# PROC054D_System_LED.net
KiCad netlist of a schematic drawn in Altium Designer
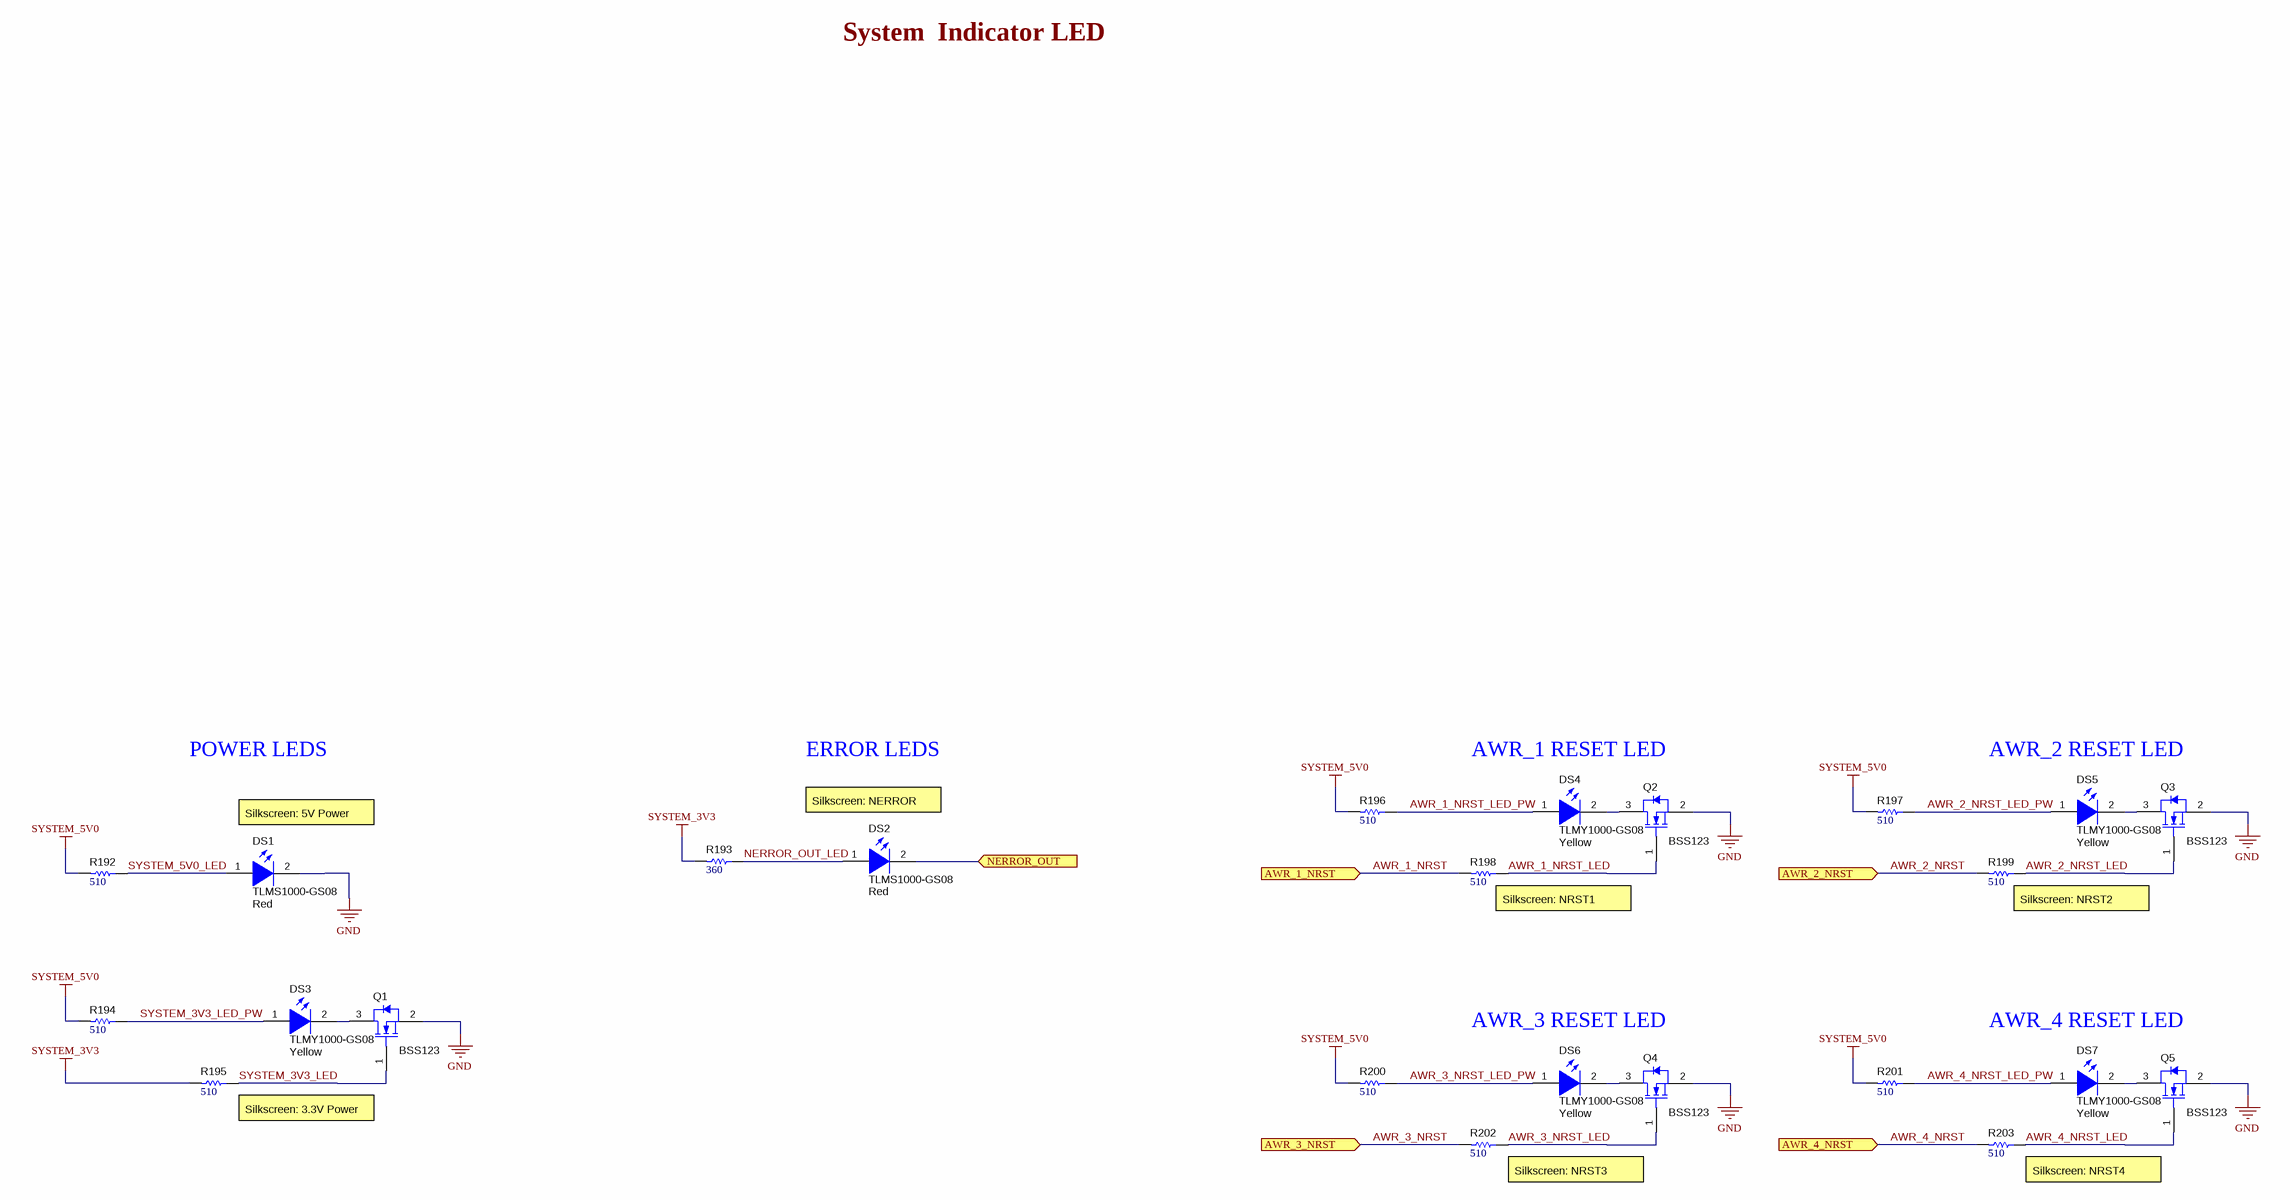
[diagram p0: PROC054D_System_LED.SchDoc]

(export (version "E")
  (design (tool "Eeschema 10.0.6"))
  (components
    (comp (ref "DS1")
      (value "TLMS1000-GS08")
      (footprint "TLMx1000_Red")
      (description "LED, Red, SMD")
      (fields
        (field (name "ALTIUM_VALUE") "Red")
        (field (name "MANUFACTURER") "Vishay-Semiconductor")
        (field (name "PUBLISHER") "Texas Instruments")
      )
      (libsource (lib "Altium Vault - TI") (part "LED"))
    )
    (comp (ref "DS2")
      (value "TLMS1000-GS08")
      (footprint "TLMx1000_Red")
      (description "LED, Red, SMD")
      (fields
        (field (name "ALTIUM_VALUE") "Red")
        (field (name "MANUFACTURER") "Vishay-Semiconductor")
        (field (name "PUBLISHER") "Texas Instruments")
      )
      (libsource (lib "Altium Vault - TI") (part "LED"))
    )
    (comp (ref "DS3")
      (value "TLMY1000-GS08")
      (footprint "TLMx1000_Yellow")
      (description "LED, Yellow, SMD")
      (fields
        (field (name "ALTIUM_VALUE") "Yellow")
        (field (name "MANUFACTURER") "Vishay-Semiconductor")
        (field (name "PUBLISHER") "Texas Instruments")
      )
      (libsource (lib "Altium Vault - TI") (part "LED"))
    )
    (comp (ref "DS4")
      (value "TLMY1000-GS08")
      (footprint "TLMx1000_Yellow")
      (description "LED, Yellow, SMD")
      (fields
        (field (name "ALTIUM_VALUE") "Yellow")
        (field (name "MANUFACTURER") "Vishay-Semiconductor")
        (field (name "PUBLISHER") "Texas Instruments")
      )
      (libsource (lib "Altium Vault - TI") (part "LED"))
    )
    (comp (ref "DS5")
      (value "TLMY1000-GS08")
      (footprint "TLMx1000_Yellow")
      (description "LED, Yellow, SMD")
      (fields
        (field (name "ALTIUM_VALUE") "Yellow")
        (field (name "MANUFACTURER") "Vishay-Semiconductor")
        (field (name "PUBLISHER") "Texas Instruments")
      )
      (libsource (lib "Altium Vault - TI") (part "LED"))
    )
    (comp (ref "DS6")
      (value "TLMY1000-GS08")
      (footprint "TLMx1000_Yellow")
      (description "LED, Yellow, SMD")
      (fields
        (field (name "ALTIUM_VALUE") "Yellow")
        (field (name "MANUFACTURER") "Vishay-Semiconductor")
        (field (name "PUBLISHER") "Texas Instruments")
      )
      (libsource (lib "Altium Vault - TI") (part "LED"))
    )
    (comp (ref "DS7")
      (value "TLMY1000-GS08")
      (footprint "TLMx1000_Yellow")
      (description "LED, Yellow, SMD")
      (fields
        (field (name "ALTIUM_VALUE") "Yellow")
        (field (name "MANUFACTURER") "Vishay-Semiconductor")
        (field (name "PUBLISHER") "Texas Instruments")
      )
      (libsource (lib "Altium Vault - TI") (part "LED"))
    )
    (comp (ref "Q1")
      (value "BSS123")
      (footprint "SOT-23")
      (description "MOSFET, N-CH, 100 V, 0.17 A, SOT-23")
      (fields
        (field (name "MANUFACTURER") "Fairchild Semiconductor")
        (field (name "PUBLISHER") "Texas Instruments")
      )
      (libsource (lib "Altium Vault - TI") (part "MOSFET_N_D3G1S2"))
    )
    (comp (ref "Q2")
      (value "BSS123")
      (footprint "SOT-23")
      (description "MOSFET, N-CH, 100 V, 0.17 A, SOT-23")
      (fields
        (field (name "MANUFACTURER") "Fairchild Semiconductor")
        (field (name "PUBLISHER") "Texas Instruments")
      )
      (libsource (lib "Altium Vault - TI") (part "MOSFET_N_D3G1S2"))
    )
    (comp (ref "Q3")
      (value "BSS123")
      (footprint "SOT-23")
      (description "MOSFET, N-CH, 100 V, 0.17 A, SOT-23")
      (fields
        (field (name "MANUFACTURER") "Fairchild Semiconductor")
        (field (name "PUBLISHER") "Texas Instruments")
      )
      (libsource (lib "Altium Vault - TI") (part "MOSFET_N_D3G1S2"))
    )
    (comp (ref "Q4")
      (value "BSS123")
      (footprint "SOT-23")
      (description "MOSFET, N-CH, 100 V, 0.17 A, SOT-23")
      (fields
        (field (name "MANUFACTURER") "Fairchild Semiconductor")
        (field (name "PUBLISHER") "Texas Instruments")
      )
      (libsource (lib "Altium Vault - TI") (part "MOSFET_N_D3G1S2"))
    )
    (comp (ref "Q5")
      (value "BSS123")
      (footprint "SOT-23")
      (description "MOSFET, N-CH, 100 V, 0.17 A, SOT-23")
      (fields
        (field (name "MANUFACTURER") "Fairchild Semiconductor")
        (field (name "PUBLISHER") "Texas Instruments")
      )
      (libsource (lib "Altium Vault - TI") (part "MOSFET_N_D3G1S2"))
    )
    (comp (ref "R192")
      (value "ERJ-2GEJ511X")
      (footprint "0402")
      (description "RES, 510, 5%, 0.1 W, AEC-Q200 Grade 0, 0402")
      (fields (field (name "MANUFACTURER") "Panasonic") (field (name "VALUEDISPLAYED") "510"))
      (libsource (lib "Altium Vault - TI") (part "Resistor"))
    )
    (comp (ref "R193")
      (value "ERJ-2GEJ361X")
      (footprint "0402")
      (description "RES, 360, 5%, 0.1 W, AEC-Q200 Grade 0, 0402")
      (fields (field (name "MANUFACTURER") "Panasonic") (field (name "VALUEDISPLAYED") "360"))
      (libsource (lib "Altium Vault - TI") (part "Resistor"))
    )
    (comp (ref "R194")
      (value "ERJ-2GEJ511X")
      (footprint "0402")
      (description "RES, 510, 5%, 0.1 W, AEC-Q200 Grade 0, 0402")
      (fields (field (name "MANUFACTURER") "Panasonic") (field (name "VALUEDISPLAYED") "510"))
      (libsource (lib "Altium Vault - TI") (part "Resistor"))
    )
    (comp (ref "R195")
      (value "ERJ-2GEJ511X")
      (footprint "0402")
      (description "RES, 510, 5%, 0.1 W, AEC-Q200 Grade 0, 0402")
      (fields (field (name "MANUFACTURER") "Panasonic") (field (name "VALUEDISPLAYED") "510"))
      (libsource (lib "Altium Vault - TI") (part "Resistor"))
    )
    (comp (ref "R196")
      (value "ERJ-2GEJ511X")
      (footprint "0402")
      (description "RES, 510, 5%, 0.1 W, AEC-Q200 Grade 0, 0402")
      (fields (field (name "MANUFACTURER") "Panasonic") (field (name "VALUEDISPLAYED") "510"))
      (libsource (lib "Altium Vault - TI") (part "Resistor"))
    )
    (comp (ref "R197")
      (value "ERJ-2GEJ511X")
      (footprint "0402")
      (description "RES, 510, 5%, 0.1 W, AEC-Q200 Grade 0, 0402")
      (fields (field (name "MANUFACTURER") "Panasonic") (field (name "VALUEDISPLAYED") "510"))
      (libsource (lib "Altium Vault - TI") (part "Resistor"))
    )
    (comp (ref "R198")
      (value "ERJ-2GEJ511X")
      (footprint "0402")
      (description "RES, 510, 5%, 0.1 W, AEC-Q200 Grade 0, 0402")
      (fields (field (name "MANUFACTURER") "Panasonic") (field (name "VALUEDISPLAYED") "510"))
      (libsource (lib "Altium Vault - TI") (part "Resistor"))
    )
    (comp (ref "R199")
      (value "ERJ-2GEJ511X")
      (footprint "0402")
      (description "RES, 510, 5%, 0.1 W, AEC-Q200 Grade 0, 0402")
      (fields (field (name "MANUFACTURER") "Panasonic") (field (name "VALUEDISPLAYED") "510"))
      (libsource (lib "Altium Vault - TI") (part "Resistor"))
    )
    (comp (ref "R200")
      (value "ERJ-2GEJ511X")
      (footprint "0402")
      (description "RES, 510, 5%, 0.1 W, AEC-Q200 Grade 0, 0402")
      (fields (field (name "MANUFACTURER") "Panasonic") (field (name "VALUEDISPLAYED") "510"))
      (libsource (lib "Altium Vault - TI") (part "Resistor"))
    )
    (comp (ref "R201")
      (value "ERJ-2GEJ511X")
      (footprint "0402")
      (description "RES, 510, 5%, 0.1 W, AEC-Q200 Grade 0, 0402")
      (fields (field (name "MANUFACTURER") "Panasonic") (field (name "VALUEDISPLAYED") "510"))
      (libsource (lib "Altium Vault - TI") (part "Resistor"))
    )
    (comp (ref "R202")
      (value "ERJ-2GEJ511X")
      (footprint "0402")
      (description "RES, 510, 5%, 0.1 W, AEC-Q200 Grade 0, 0402")
      (fields (field (name "MANUFACTURER") "Panasonic") (field (name "VALUEDISPLAYED") "510"))
      (libsource (lib "Altium Vault - TI") (part "Resistor"))
    )
    (comp (ref "R203")
      (value "ERJ-2GEJ511X")
      (footprint "0402")
      (description "RES, 510, 5%, 0.1 W, AEC-Q200 Grade 0, 0402")
      (fields (field (name "MANUFACTURER") "Panasonic") (field (name "VALUEDISPLAYED") "510"))
      (libsource (lib "Altium Vault - TI") (part "Resistor"))
    )
  )
  (nets
    (net (code "1") (name "/AWR_1_NRST") (class "Default")
      (node (ref "R198") (pin "2") (pinfunction "2_2") (pintype "passive"))
    )
    (net (code "2") (name "/AWR_1_NRST_LED") (class "Default")
      (node (ref "Q2") (pin "1") (pinfunction "G_1") (pintype "passive"))
      (node (ref "R198") (pin "1") (pinfunction "1_1") (pintype "passive"))
    )
    (net (code "3") (name "/AWR_1_NRST_LED_PW") (class "Default")
      (node (ref "DS4") (pin "1") (pinfunction "A_1") (pintype "passive"))
      (node (ref "R196") (pin "1") (pinfunction "1_1") (pintype "passive"))
    )
    (net (code "4") (name "/AWR_2_NRST") (class "Default")
      (node (ref "R199") (pin "2") (pinfunction "2_2") (pintype "passive"))
    )
    (net (code "5") (name "/AWR_2_NRST_LED") (class "Default")
      (node (ref "Q3") (pin "1") (pinfunction "G_1") (pintype "passive"))
      (node (ref "R199") (pin "1") (pinfunction "1_1") (pintype "passive"))
    )
    (net (code "6") (name "/AWR_2_NRST_LED_PW") (class "Default")
      (node (ref "DS5") (pin "1") (pinfunction "A_1") (pintype "passive"))
      (node (ref "R197") (pin "1") (pinfunction "1_1") (pintype "passive"))
    )
    (net (code "7") (name "/AWR_3_NRST") (class "Default")
      (node (ref "R202") (pin "2") (pinfunction "2_2") (pintype "passive"))
    )
    (net (code "8") (name "/AWR_3_NRST_LED") (class "Default")
      (node (ref "Q4") (pin "1") (pinfunction "G_1") (pintype "passive"))
      (node (ref "R202") (pin "1") (pinfunction "1_1") (pintype "passive"))
    )
    (net (code "9") (name "/AWR_3_NRST_LED_PW") (class "Default")
      (node (ref "DS6") (pin "1") (pinfunction "A_1") (pintype "passive"))
      (node (ref "R200") (pin "1") (pinfunction "1_1") (pintype "passive"))
    )
    (net (code "10") (name "/AWR_4_NRST") (class "Default")
      (node (ref "R203") (pin "2") (pinfunction "2_2") (pintype "passive"))
    )
    (net (code "11") (name "/AWR_4_NRST_LED") (class "Default")
      (node (ref "Q5") (pin "1") (pinfunction "G_1") (pintype "passive"))
      (node (ref "R203") (pin "1") (pinfunction "1_1") (pintype "passive"))
    )
    (net (code "12") (name "/AWR_4_NRST_LED_PW") (class "Default")
      (node (ref "DS7") (pin "1") (pinfunction "A_1") (pintype "passive"))
      (node (ref "R201") (pin "1") (pinfunction "1_1") (pintype "passive"))
    )
    (net (code "13") (name "/NERROR_OUT") (class "Default")
      (node (ref "DS2") (pin "2") (pinfunction "K_2") (pintype "passive"))
    )
    (net (code "14") (name "/NERROR_OUT_LED") (class "Default")
      (node (ref "DS2") (pin "1") (pinfunction "A_1") (pintype "passive"))
      (node (ref "R193") (pin "1") (pinfunction "1_1") (pintype "passive"))
    )
    (net (code "15") (name "/SYSTEM_3V3_LED") (class "Default")
      (node (ref "Q1") (pin "1") (pinfunction "G_1") (pintype "passive"))
      (node (ref "R195") (pin "1") (pinfunction "1_1") (pintype "passive"))
    )
    (net (code "16") (name "/SYSTEM_3V3_LED_PW") (class "Default")
      (node (ref "DS3") (pin "1") (pinfunction "A_1") (pintype "passive"))
      (node (ref "R194") (pin "1") (pinfunction "1_1") (pintype "passive"))
    )
    (net (code "17") (name "/SYSTEM_5V0_LED") (class "Default")
      (node (ref "DS1") (pin "1") (pinfunction "A_1") (pintype "passive"))
      (node (ref "R192") (pin "1") (pinfunction "1_1") (pintype "passive"))
    )
    (net (code "18") (name "GND") (class "Default")
      (node (ref "DS1") (pin "2") (pinfunction "K_2") (pintype "passive"))
      (node (ref "Q1") (pin "2") (pinfunction "S_2") (pintype "passive"))
      (node (ref "Q2") (pin "2") (pinfunction "S_2") (pintype "passive"))
      (node (ref "Q3") (pin "2") (pinfunction "S_2") (pintype "passive"))
      (node (ref "Q4") (pin "2") (pinfunction "S_2") (pintype "passive"))
      (node (ref "Q5") (pin "2") (pinfunction "S_2") (pintype "passive"))
    )
    (net (code "19") (name "Net-(DS3-K)") (class "Default")
      (node (ref "DS3") (pin "2") (pinfunction "K_2") (pintype "passive"))
      (node (ref "Q1") (pin "3") (pinfunction "D_3") (pintype "passive"))
    )
    (net (code "20") (name "Net-(DS4-K)") (class "Default")
      (node (ref "DS4") (pin "2") (pinfunction "K_2") (pintype "passive"))
      (node (ref "Q2") (pin "3") (pinfunction "D_3") (pintype "passive"))
    )
    (net (code "21") (name "Net-(DS5-K)") (class "Default")
      (node (ref "DS5") (pin "2") (pinfunction "K_2") (pintype "passive"))
      (node (ref "Q3") (pin "3") (pinfunction "D_3") (pintype "passive"))
    )
    (net (code "22") (name "Net-(DS6-K)") (class "Default")
      (node (ref "DS6") (pin "2") (pinfunction "K_2") (pintype "passive"))
      (node (ref "Q4") (pin "3") (pinfunction "D_3") (pintype "passive"))
    )
    (net (code "23") (name "Net-(DS7-K)") (class "Default")
      (node (ref "DS7") (pin "2") (pinfunction "K_2") (pintype "passive"))
      (node (ref "Q5") (pin "3") (pinfunction "D_3") (pintype "passive"))
    )
    (net (code "24") (name "SYSTEM_3V3") (class "Default")
      (node (ref "R193") (pin "2") (pinfunction "2_2") (pintype "passive"))
      (node (ref "R195") (pin "2") (pinfunction "2_2") (pintype "passive"))
    )
    (net (code "25") (name "SYSTEM_5V0") (class "Default")
      (node (ref "R192") (pin "2") (pinfunction "2_2") (pintype "passive"))
      (node (ref "R194") (pin "2") (pinfunction "2_2") (pintype "passive"))
      (node (ref "R196") (pin "2") (pinfunction "2_2") (pintype "passive"))
      (node (ref "R197") (pin "2") (pinfunction "2_2") (pintype "passive"))
      (node (ref "R200") (pin "2") (pinfunction "2_2") (pintype "passive"))
      (node (ref "R201") (pin "2") (pinfunction "2_2") (pintype "passive"))
    )
  )
)
